# Sheet4.net
KiCad netlist of a schematic drawn in Altium Designer
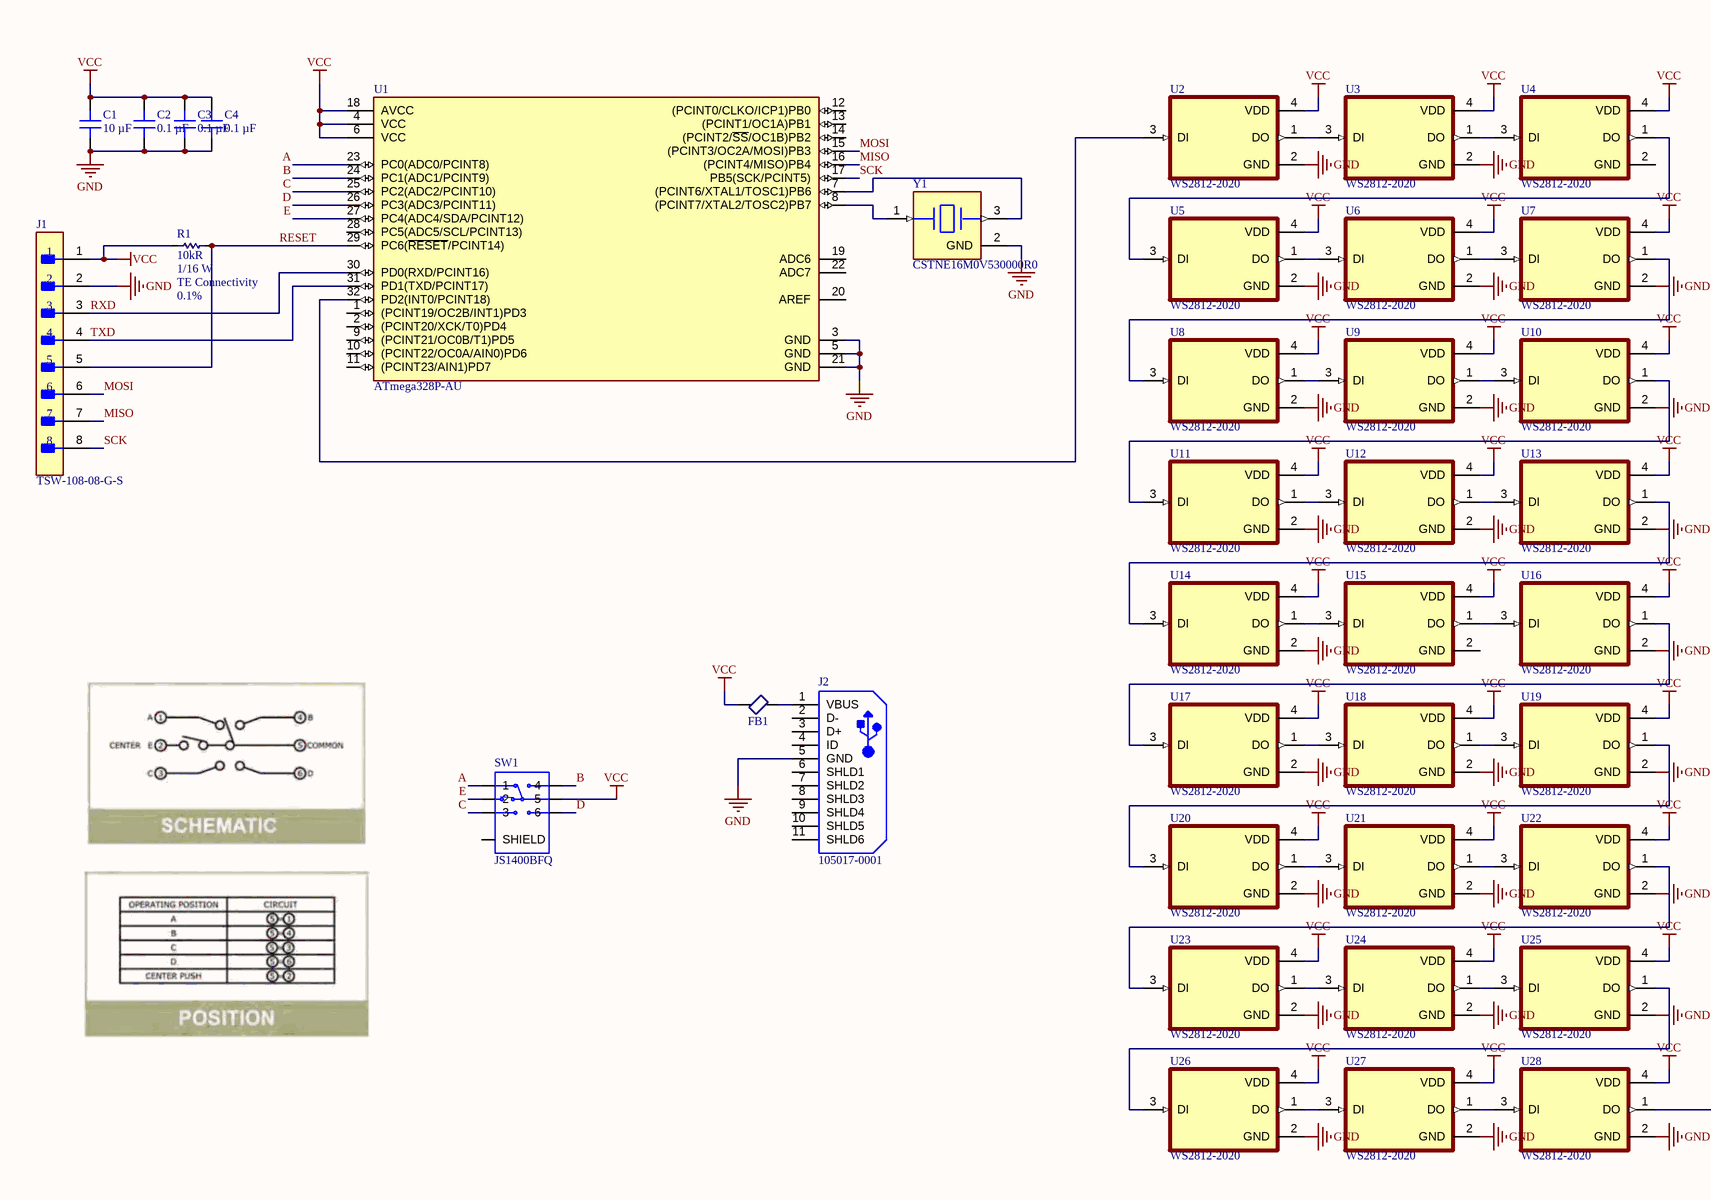
[diagram p0: Sheet4.SchDoc, left]
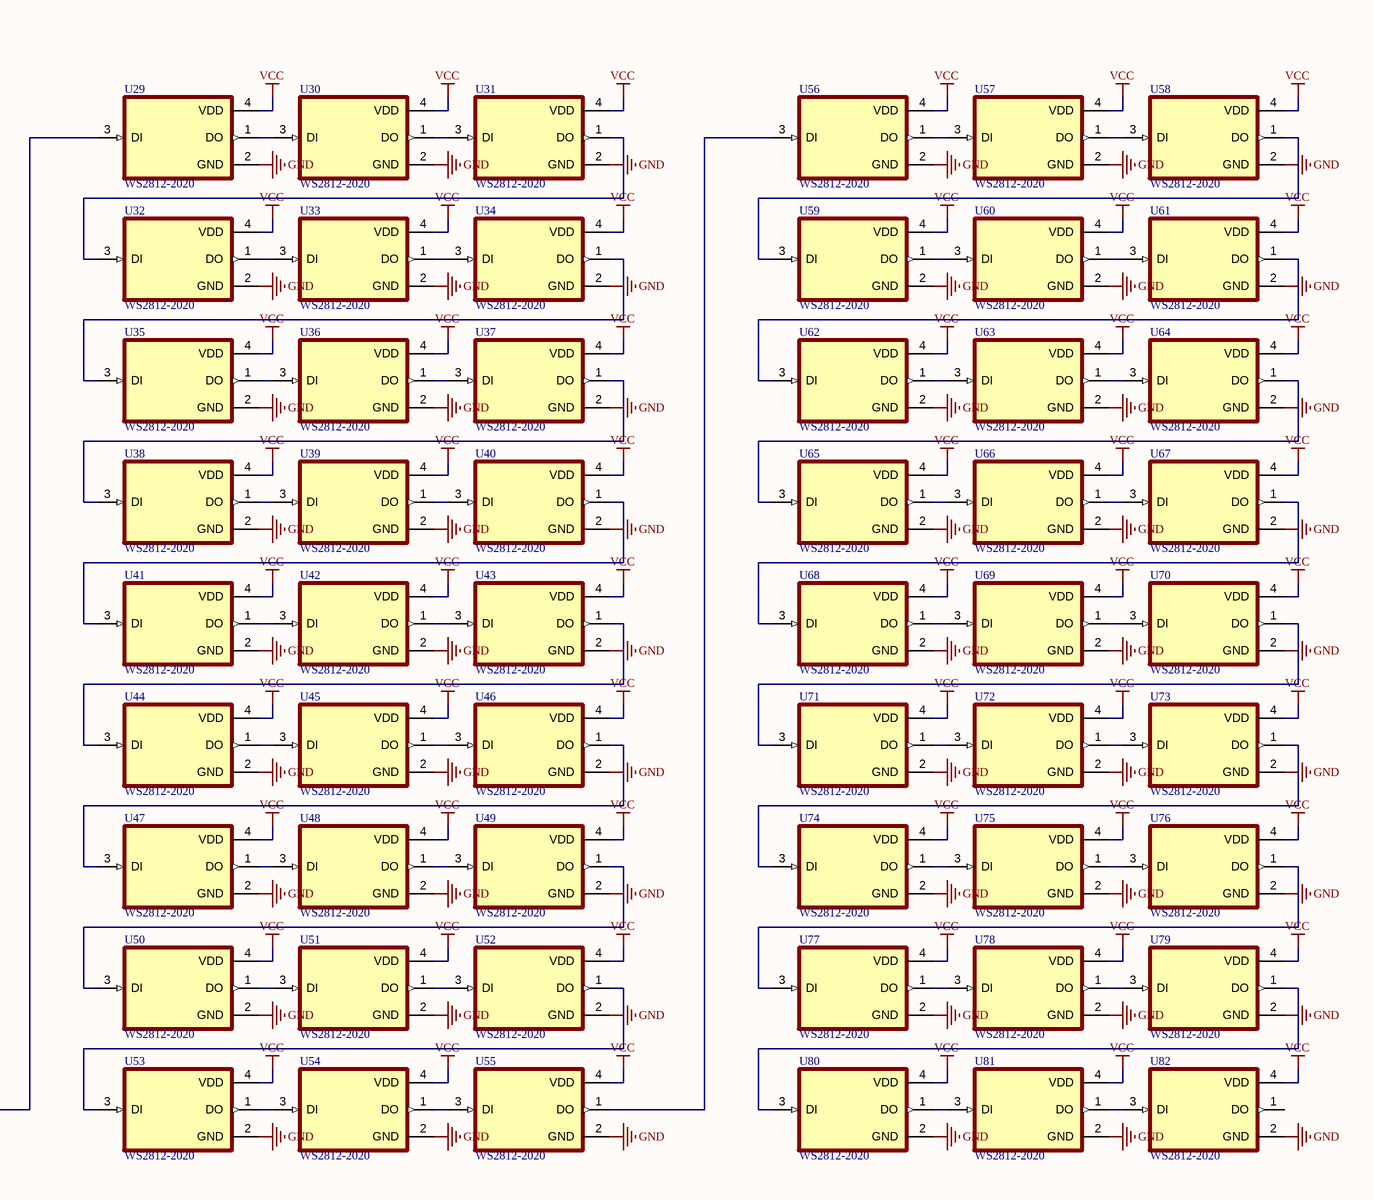
[diagram p1: Sheet4.SchDoc, right]

(export (version "E")
  (design (tool "Eeschema 10.0.6"))
  (components
    (comp (ref "C1")
      (value "10 µF")
      (footprint "CAP 0402_1005")
      (description "CAP CER 10UF 10V X5R 0402")
      (fields
        (field (name "PART NUMBER") "CL05A106MP5NUNC")
        (field (name "MANUFACTURER") "Samsung Electro-Mechanics")
      )
      (libsource (lib "Celestial Altium Library - altium_library") (part "Capacitor"))
    )
    (comp (ref "C2")
      (value "0.1 µF")
      (footprint "CAP 0402_1005")
      (description "CAP CER 0.1UF 10V X5R 0402")
      (fields
        (field (name "PART NUMBER") "CL05A104KP5NNNC")
        (field (name "MANUFACTURER") "Samsung Electro-Mechanics")
      )
      (libsource (lib "Celestial Altium Library - altium_library") (part "Capacitor"))
    )
    (comp (ref "C3")
      (value "0.1 µF")
      (footprint "CAP 0402_1005")
      (description "CAP CER 0.1UF 10V X5R 0402")
      (fields
        (field (name "PART NUMBER") "CL05A104KP5NNNC")
        (field (name "MANUFACTURER") "Samsung Electro-Mechanics")
      )
      (libsource (lib "Celestial Altium Library - altium_library") (part "Capacitor"))
    )
    (comp (ref "C4")
      (value "0.1 µF")
      (footprint "CAP 0402_1005")
      (description "CAP CER 0.1UF 10V X5R 0402")
      (fields
        (field (name "PART NUMBER") "CL05A104KP5NNNC")
        (field (name "MANUFACTURER") "Samsung Electro-Mechanics")
      )
      (libsource (lib "Celestial Altium Library - altium_library") (part "Capacitor"))
    )
    (comp (ref "FB1")
      (value "FB_330R_1.5A_0603")
      (footprint "FP-BLM18-0_15-t0_5-IPC_C")
      (description "Ferrite Beads Multi-Layer 330Ohm 25% 100MHz 1.5A 70mOhm DCR 0603 Paper T/R")
      (libsource (lib "Kennesaw Motorsports") (part "5f30dd21d616792df468990f7003faa"))
    )
    (comp (ref "J1")
      (value "TSW-108-08-G-S")
      (footprint "FP-TSW-108-08-G-S-MFG")
      (description "CONN HEADER VERT 8POS 2.54MM")
      (fields
        (field (name "MANUFACTURER") "Samtec")
        (field (name "OCTOPART") "https://octopart.com/tsw-108-08-g-s-samtec-272653")
      )
      (libsource (lib "Altium Content Vault") (part "99ec2b232beb5d2356d4d77f6a047f0"))
    )
    (comp (ref "J2")
      (value "105017-0001")
      (footprint "USB-MICRO-B_V")
      (fields (field (name "MANUFACTURER") "Molex"))
      (libsource (lib "Altium Content Vault") (part "USB-5-6SHLD"))
    )
    (comp (ref "R1")
      (value "RN73C1E10KBTG")
      (footprint "FP-RN731E-IPC_B")
      (description "RES 10K 0402 1/16W, RN73C1E10KBTG")
      (fields
        (field (name "RESISTANCE") "10kR")
        (field (name "POWER") "1/16 W")
        (field (name "MANUFACTURER") "TE Connectivity")
        (field (name "TOLERANCE") "0.1%")
        (field (name "PARTNUMBER") "RN73C1J4R99BTD")
        (field (name "SOURCE") "GoodResistor.SchLib")
      )
      (libsource (lib "Kennesaw Motorsports") (part "RN73C1E1K0BTD"))
    )
    (comp (ref "SW1")
      (value "JS1400BFQ")
      (footprint "SW_JS1400BFQ")
      (description "Navigation Switch, 2 - Axis Digital (Mechanical Switch) Output")
      (fields (field (name "DIGI-KEY_PART_NUMBER") "EG5858-ND") (field (name "MF") "E-Switch"))
      (libsource (lib "Kennesaw Motorsports") (part "JS1400BFQ"))
    )
    (comp (ref "U1")
      (value "ATmega328P-AU")
      (footprint "FP-32A-MFG")
      (description "IC MCU 8BIT 32KB FLASH 32TQFP")
      (fields
        (field (name "MANUFACTURER") "Microchip")
        (field (name "OCTOPART") "https://octopart.com/atmega328p-au-microchip-77760215")
      )
      (libsource (lib "Altium Content Vault") (part "f5fbdcb2c0c597ef7d3dd1575aef21a"))
    )
    (comp (ref "U2")
      (value "WS2812-2020")
      (footprint "LED_WS2812-2020")
      (description "Intelligent control LED integrated light source, WS2812-2020")
      (libsource (lib "Kennesaw Motorsports") (part "WS2812-2020"))
    )
    (comp (ref "U3")
      (value "WS2812-2020")
      (footprint "LED_WS2812-2020")
      (description "Intelligent control LED integrated light source, WS2812-2020")
      (libsource (lib "Kennesaw Motorsports") (part "WS2812-2020"))
    )
    (comp (ref "U4")
      (value "WS2812-2020")
      (footprint "LED_WS2812-2020")
      (description "Intelligent control LED integrated light source, WS2812-2020")
      (libsource (lib "Kennesaw Motorsports") (part "WS2812-2020"))
    )
    (comp (ref "U5")
      (value "WS2812-2020")
      (footprint "LED_WS2812-2020")
      (description "Intelligent control LED integrated light source, WS2812-2020")
      (libsource (lib "Kennesaw Motorsports") (part "WS2812-2020"))
    )
    (comp (ref "U6")
      (value "WS2812-2020")
      (footprint "LED_WS2812-2020")
      (description "Intelligent control LED integrated light source, WS2812-2020")
      (libsource (lib "Kennesaw Motorsports") (part "WS2812-2020"))
    )
    (comp (ref "U7")
      (value "WS2812-2020")
      (footprint "LED_WS2812-2020")
      (description "Intelligent control LED integrated light source, WS2812-2020")
      (libsource (lib "Kennesaw Motorsports") (part "WS2812-2020"))
    )
    (comp (ref "U8")
      (value "WS2812-2020")
      (footprint "LED_WS2812-2020")
      (description "Intelligent control LED integrated light source, WS2812-2020")
      (libsource (lib "Kennesaw Motorsports") (part "WS2812-2020"))
    )
    (comp (ref "U9")
      (value "WS2812-2020")
      (footprint "LED_WS2812-2020")
      (description "Intelligent control LED integrated light source, WS2812-2020")
      (libsource (lib "Kennesaw Motorsports") (part "WS2812-2020"))
    )
    (comp (ref "U10")
      (value "WS2812-2020")
      (footprint "LED_WS2812-2020")
      (description "Intelligent control LED integrated light source, WS2812-2020")
      (libsource (lib "Kennesaw Motorsports") (part "WS2812-2020"))
    )
    (comp (ref "U11")
      (value "WS2812-2020")
      (footprint "LED_WS2812-2020")
      (description "Intelligent control LED integrated light source, WS2812-2020")
      (libsource (lib "Kennesaw Motorsports") (part "WS2812-2020"))
    )
    (comp (ref "U12")
      (value "WS2812-2020")
      (footprint "LED_WS2812-2020")
      (description "Intelligent control LED integrated light source, WS2812-2020")
      (libsource (lib "Kennesaw Motorsports") (part "WS2812-2020"))
    )
    (comp (ref "U13")
      (value "WS2812-2020")
      (footprint "LED_WS2812-2020")
      (description "Intelligent control LED integrated light source, WS2812-2020")
      (libsource (lib "Kennesaw Motorsports") (part "WS2812-2020"))
    )
    (comp (ref "U14")
      (value "WS2812-2020")
      (footprint "LED_WS2812-2020")
      (description "Intelligent control LED integrated light source, WS2812-2020")
      (libsource (lib "Kennesaw Motorsports") (part "WS2812-2020"))
    )
    (comp (ref "U15")
      (value "WS2812-2020")
      (footprint "LED_WS2812-2020")
      (description "Intelligent control LED integrated light source, WS2812-2020")
      (libsource (lib "Kennesaw Motorsports") (part "WS2812-2020"))
    )
    (comp (ref "U16")
      (value "WS2812-2020")
      (footprint "LED_WS2812-2020")
      (description "Intelligent control LED integrated light source, WS2812-2020")
      (libsource (lib "Kennesaw Motorsports") (part "WS2812-2020"))
    )
    (comp (ref "U17")
      (value "WS2812-2020")
      (footprint "LED_WS2812-2020")
      (description "Intelligent control LED integrated light source, WS2812-2020")
      (libsource (lib "Kennesaw Motorsports") (part "WS2812-2020"))
    )
    (comp (ref "U18")
      (value "WS2812-2020")
      (footprint "LED_WS2812-2020")
      (description "Intelligent control LED integrated light source, WS2812-2020")
      (libsource (lib "Kennesaw Motorsports") (part "WS2812-2020"))
    )
    (comp (ref "U19")
      (value "WS2812-2020")
      (footprint "LED_WS2812-2020")
      (description "Intelligent control LED integrated light source, WS2812-2020")
      (libsource (lib "Kennesaw Motorsports") (part "WS2812-2020"))
    )
    (comp (ref "U20")
      (value "WS2812-2020")
      (footprint "LED_WS2812-2020")
      (description "Intelligent control LED integrated light source, WS2812-2020")
      (libsource (lib "Kennesaw Motorsports") (part "WS2812-2020"))
    )
    (comp (ref "U21")
      (value "WS2812-2020")
      (footprint "LED_WS2812-2020")
      (description "Intelligent control LED integrated light source, WS2812-2020")
      (libsource (lib "Kennesaw Motorsports") (part "WS2812-2020"))
    )
    (comp (ref "U22")
      (value "WS2812-2020")
      (footprint "LED_WS2812-2020")
      (description "Intelligent control LED integrated light source, WS2812-2020")
      (libsource (lib "Kennesaw Motorsports") (part "WS2812-2020"))
    )
    (comp (ref "U23")
      (value "WS2812-2020")
      (footprint "LED_WS2812-2020")
      (description "Intelligent control LED integrated light source, WS2812-2020")
      (libsource (lib "Kennesaw Motorsports") (part "WS2812-2020"))
    )
    (comp (ref "U24")
      (value "WS2812-2020")
      (footprint "LED_WS2812-2020")
      (description "Intelligent control LED integrated light source, WS2812-2020")
      (libsource (lib "Kennesaw Motorsports") (part "WS2812-2020"))
    )
    (comp (ref "U25")
      (value "WS2812-2020")
      (footprint "LED_WS2812-2020")
      (description "Intelligent control LED integrated light source, WS2812-2020")
      (libsource (lib "Kennesaw Motorsports") (part "WS2812-2020"))
    )
    (comp (ref "U26")
      (value "WS2812-2020")
      (footprint "LED_WS2812-2020")
      (description "Intelligent control LED integrated light source, WS2812-2020")
      (libsource (lib "Kennesaw Motorsports") (part "WS2812-2020"))
    )
    (comp (ref "U27")
      (value "WS2812-2020")
      (footprint "LED_WS2812-2020")
      (description "Intelligent control LED integrated light source, WS2812-2020")
      (libsource (lib "Kennesaw Motorsports") (part "WS2812-2020"))
    )
    (comp (ref "U28")
      (value "WS2812-2020")
      (footprint "LED_WS2812-2020")
      (description "Intelligent control LED integrated light source, WS2812-2020")
      (libsource (lib "Kennesaw Motorsports") (part "WS2812-2020"))
    )
    (comp (ref "U29")
      (value "WS2812-2020")
      (footprint "LED_WS2812-2020")
      (description "Intelligent control LED integrated light source, WS2812-2020")
      (libsource (lib "Kennesaw Motorsports") (part "WS2812-2020"))
    )
    (comp (ref "U30")
      (value "WS2812-2020")
      (footprint "LED_WS2812-2020")
      (description "Intelligent control LED integrated light source, WS2812-2020")
      (libsource (lib "Kennesaw Motorsports") (part "WS2812-2020"))
    )
    (comp (ref "U31")
      (value "WS2812-2020")
      (footprint "LED_WS2812-2020")
      (description "Intelligent control LED integrated light source, WS2812-2020")
      (libsource (lib "Kennesaw Motorsports") (part "WS2812-2020"))
    )
    (comp (ref "U32")
      (value "WS2812-2020")
      (footprint "LED_WS2812-2020")
      (description "Intelligent control LED integrated light source, WS2812-2020")
      (libsource (lib "Kennesaw Motorsports") (part "WS2812-2020"))
    )
    (comp (ref "U33")
      (value "WS2812-2020")
      (footprint "LED_WS2812-2020")
      (description "Intelligent control LED integrated light source, WS2812-2020")
      (libsource (lib "Kennesaw Motorsports") (part "WS2812-2020"))
    )
    (comp (ref "U34")
      (value "WS2812-2020")
      (footprint "LED_WS2812-2020")
      (description "Intelligent control LED integrated light source, WS2812-2020")
      (libsource (lib "Kennesaw Motorsports") (part "WS2812-2020"))
    )
    (comp (ref "U35")
      (value "WS2812-2020")
      (footprint "LED_WS2812-2020")
      (description "Intelligent control LED integrated light source, WS2812-2020")
      (libsource (lib "Kennesaw Motorsports") (part "WS2812-2020"))
    )
    (comp (ref "U36")
      (value "WS2812-2020")
      (footprint "LED_WS2812-2020")
      (description "Intelligent control LED integrated light source, WS2812-2020")
      (libsource (lib "Kennesaw Motorsports") (part "WS2812-2020"))
    )
    (comp (ref "U37")
      (value "WS2812-2020")
      (footprint "LED_WS2812-2020")
      (description "Intelligent control LED integrated light source, WS2812-2020")
      (libsource (lib "Kennesaw Motorsports") (part "WS2812-2020"))
    )
    (comp (ref "U38")
      (value "WS2812-2020")
      (footprint "LED_WS2812-2020")
      (description "Intelligent control LED integrated light source, WS2812-2020")
      (libsource (lib "Kennesaw Motorsports") (part "WS2812-2020"))
    )
    (comp (ref "U39")
      (value "WS2812-2020")
      (footprint "LED_WS2812-2020")
      (description "Intelligent control LED integrated light source, WS2812-2020")
      (libsource (lib "Kennesaw Motorsports") (part "WS2812-2020"))
    )
    (comp (ref "U40")
      (value "WS2812-2020")
      (footprint "LED_WS2812-2020")
      (description "Intelligent control LED integrated light source, WS2812-2020")
      (libsource (lib "Kennesaw Motorsports") (part "WS2812-2020"))
    )
    (comp (ref "U41")
      (value "WS2812-2020")
      (footprint "LED_WS2812-2020")
      (description "Intelligent control LED integrated light source, WS2812-2020")
      (libsource (lib "Kennesaw Motorsports") (part "WS2812-2020"))
    )
    (comp (ref "U42")
      (value "WS2812-2020")
      (footprint "LED_WS2812-2020")
      (description "Intelligent control LED integrated light source, WS2812-2020")
      (libsource (lib "Kennesaw Motorsports") (part "WS2812-2020"))
    )
    (comp (ref "U43")
      (value "WS2812-2020")
      (footprint "LED_WS2812-2020")
      (description "Intelligent control LED integrated light source, WS2812-2020")
      (libsource (lib "Kennesaw Motorsports") (part "WS2812-2020"))
    )
    (comp (ref "U44")
      (value "WS2812-2020")
      (footprint "LED_WS2812-2020")
      (description "Intelligent control LED integrated light source, WS2812-2020")
      (libsource (lib "Kennesaw Motorsports") (part "WS2812-2020"))
    )
    (comp (ref "U45")
      (value "WS2812-2020")
      (footprint "LED_WS2812-2020")
      (description "Intelligent control LED integrated light source, WS2812-2020")
      (libsource (lib "Kennesaw Motorsports") (part "WS2812-2020"))
    )
    (comp (ref "U46")
      (value "WS2812-2020")
      (footprint "LED_WS2812-2020")
      (description "Intelligent control LED integrated light source, WS2812-2020")
      (libsource (lib "Kennesaw Motorsports") (part "WS2812-2020"))
    )
    (comp (ref "U47")
      (value "WS2812-2020")
      (footprint "LED_WS2812-2020")
      (description "Intelligent control LED integrated light source, WS2812-2020")
      (libsource (lib "Kennesaw Motorsports") (part "WS2812-2020"))
    )
    (comp (ref "U48")
      (value "WS2812-2020")
      (footprint "LED_WS2812-2020")
      (description "Intelligent control LED integrated light source, WS2812-2020")
      (libsource (lib "Kennesaw Motorsports") (part "WS2812-2020"))
    )
    (comp (ref "U49")
      (value "WS2812-2020")
      (footprint "LED_WS2812-2020")
      (description "Intelligent control LED integrated light source, WS2812-2020")
      (libsource (lib "Kennesaw Motorsports") (part "WS2812-2020"))
    )
    (comp (ref "U50")
      (value "WS2812-2020")
      (footprint "LED_WS2812-2020")
      (description "Intelligent control LED integrated light source, WS2812-2020")
      (libsource (lib "Kennesaw Motorsports") (part "WS2812-2020"))
    )
    (comp (ref "U51")
      (value "WS2812-2020")
      (footprint "LED_WS2812-2020")
      (description "Intelligent control LED integrated light source, WS2812-2020")
      (libsource (lib "Kennesaw Motorsports") (part "WS2812-2020"))
    )
    (comp (ref "U52")
      (value "WS2812-2020")
      (footprint "LED_WS2812-2020")
      (description "Intelligent control LED integrated light source, WS2812-2020")
      (libsource (lib "Kennesaw Motorsports") (part "WS2812-2020"))
    )
    (comp (ref "U53")
      (value "WS2812-2020")
      (footprint "LED_WS2812-2020")
      (description "Intelligent control LED integrated light source, WS2812-2020")
      (libsource (lib "Kennesaw Motorsports") (part "WS2812-2020"))
    )
    (comp (ref "U54")
      (value "WS2812-2020")
      (footprint "LED_WS2812-2020")
      (description "Intelligent control LED integrated light source, WS2812-2020")
      (libsource (lib "Kennesaw Motorsports") (part "WS2812-2020"))
    )
    (comp (ref "U55")
      (value "WS2812-2020")
      (footprint "LED_WS2812-2020")
      (description "Intelligent control LED integrated light source, WS2812-2020")
      (libsource (lib "Kennesaw Motorsports") (part "WS2812-2020"))
    )
    (comp (ref "U56")
      (value "WS2812-2020")
      (footprint "LED_WS2812-2020")
      (description "Intelligent control LED integrated light source, WS2812-2020")
      (libsource (lib "Kennesaw Motorsports") (part "WS2812-2020"))
    )
    (comp (ref "U57")
      (value "WS2812-2020")
      (footprint "LED_WS2812-2020")
      (description "Intelligent control LED integrated light source, WS2812-2020")
      (libsource (lib "Kennesaw Motorsports") (part "WS2812-2020"))
    )
    (comp (ref "U58")
      (value "WS2812-2020")
      (footprint "LED_WS2812-2020")
      (description "Intelligent control LED integrated light source, WS2812-2020")
      (libsource (lib "Kennesaw Motorsports") (part "WS2812-2020"))
    )
    (comp (ref "U59")
      (value "WS2812-2020")
      (footprint "LED_WS2812-2020")
      (description "Intelligent control LED integrated light source, WS2812-2020")
      (libsource (lib "Kennesaw Motorsports") (part "WS2812-2020"))
    )
    (comp (ref "U60")
      (value "WS2812-2020")
      (footprint "LED_WS2812-2020")
      (description "Intelligent control LED integrated light source, WS2812-2020")
      (libsource (lib "Kennesaw Motorsports") (part "WS2812-2020"))
    )
    (comp (ref "U61")
      (value "WS2812-2020")
      (footprint "LED_WS2812-2020")
      (description "Intelligent control LED integrated light source, WS2812-2020")
      (libsource (lib "Kennesaw Motorsports") (part "WS2812-2020"))
    )
    (comp (ref "U62")
      (value "WS2812-2020")
      (footprint "LED_WS2812-2020")
      (description "Intelligent control LED integrated light source, WS2812-2020")
      (libsource (lib "Kennesaw Motorsports") (part "WS2812-2020"))
    )
    (comp (ref "U63")
      (value "WS2812-2020")
      (footprint "LED_WS2812-2020")
      (description "Intelligent control LED integrated light source, WS2812-2020")
      (libsource (lib "Kennesaw Motorsports") (part "WS2812-2020"))
    )
    (comp (ref "U64")
      (value "WS2812-2020")
      (footprint "LED_WS2812-2020")
      (description "Intelligent control LED integrated light source, WS2812-2020")
      (libsource (lib "Kennesaw Motorsports") (part "WS2812-2020"))
    )
    (comp (ref "U65")
      (value "WS2812-2020")
      (footprint "LED_WS2812-2020")
      (description "Intelligent control LED integrated light source, WS2812-2020")
      (libsource (lib "Kennesaw Motorsports") (part "WS2812-2020"))
    )
    (comp (ref "U66")
      (value "WS2812-2020")
      (footprint "LED_WS2812-2020")
      (description "Intelligent control LED integrated light source, WS2812-2020")
      (libsource (lib "Kennesaw Motorsports") (part "WS2812-2020"))
    )
    (comp (ref "U67")
      (value "WS2812-2020")
      (footprint "LED_WS2812-2020")
      (description "Intelligent control LED integrated light source, WS2812-2020")
      (libsource (lib "Kennesaw Motorsports") (part "WS2812-2020"))
    )
    (comp (ref "U68")
      (value "WS2812-2020")
      (footprint "LED_WS2812-2020")
      (description "Intelligent control LED integrated light source, WS2812-2020")
      (libsource (lib "Kennesaw Motorsports") (part "WS2812-2020"))
    )
    (comp (ref "U69")
      (value "WS2812-2020")
      (footprint "LED_WS2812-2020")
      (description "Intelligent control LED integrated light source, WS2812-2020")
      (libsource (lib "Kennesaw Motorsports") (part "WS2812-2020"))
    )
    (comp (ref "U70")
      (value "WS2812-2020")
      (footprint "LED_WS2812-2020")
      (description "Intelligent control LED integrated light source, WS2812-2020")
      (libsource (lib "Kennesaw Motorsports") (part "WS2812-2020"))
    )
    (comp (ref "U71")
      (value "WS2812-2020")
      (footprint "LED_WS2812-2020")
      (description "Intelligent control LED integrated light source, WS2812-2020")
      (libsource (lib "Kennesaw Motorsports") (part "WS2812-2020"))
    )
    (comp (ref "U72")
      (value "WS2812-2020")
      (footprint "LED_WS2812-2020")
      (description "Intelligent control LED integrated light source, WS2812-2020")
      (libsource (lib "Kennesaw Motorsports") (part "WS2812-2020"))
    )
    (comp (ref "U73")
      (value "WS2812-2020")
      (footprint "LED_WS2812-2020")
      (description "Intelligent control LED integrated light source, WS2812-2020")
      (libsource (lib "Kennesaw Motorsports") (part "WS2812-2020"))
    )
    (comp (ref "U74")
      (value "WS2812-2020")
      (footprint "LED_WS2812-2020")
      (description "Intelligent control LED integrated light source, WS2812-2020")
      (libsource (lib "Kennesaw Motorsports") (part "WS2812-2020"))
    )
    (comp (ref "U75")
      (value "WS2812-2020")
      (footprint "LED_WS2812-2020")
      (description "Intelligent control LED integrated light source, WS2812-2020")
      (libsource (lib "Kennesaw Motorsports") (part "WS2812-2020"))
    )
    (comp (ref "U76")
      (value "WS2812-2020")
      (footprint "LED_WS2812-2020")
      (description "Intelligent control LED integrated light source, WS2812-2020")
      (libsource (lib "Kennesaw Motorsports") (part "WS2812-2020"))
    )
    (comp (ref "U77")
      (value "WS2812-2020")
      (footprint "LED_WS2812-2020")
      (description "Intelligent control LED integrated light source, WS2812-2020")
      (libsource (lib "Kennesaw Motorsports") (part "WS2812-2020"))
    )
    (comp (ref "U78")
      (value "WS2812-2020")
      (footprint "LED_WS2812-2020")
      (description "Intelligent control LED integrated light source, WS2812-2020")
      (libsource (lib "Kennesaw Motorsports") (part "WS2812-2020"))
    )
    (comp (ref "U79")
      (value "WS2812-2020")
      (footprint "LED_WS2812-2020")
      (description "Intelligent control LED integrated light source, WS2812-2020")
      (libsource (lib "Kennesaw Motorsports") (part "WS2812-2020"))
    )
    (comp (ref "U80")
      (value "WS2812-2020")
      (footprint "LED_WS2812-2020")
      (description "Intelligent control LED integrated light source, WS2812-2020")
      (libsource (lib "Kennesaw Motorsports") (part "WS2812-2020"))
    )
    (comp (ref "U81")
      (value "WS2812-2020")
      (footprint "LED_WS2812-2020")
      (description "Intelligent control LED integrated light source, WS2812-2020")
      (libsource (lib "Kennesaw Motorsports") (part "WS2812-2020"))
    )
    (comp (ref "U82")
      (value "WS2812-2020")
      (footprint "LED_WS2812-2020")
      (description "Intelligent control LED integrated light source, WS2812-2020")
      (libsource (lib "Kennesaw Motorsports") (part "WS2812-2020"))
    )
    (comp (ref "Y1")
      (value "CSTNE16M0V530000R0")
      (footprint "FP-CSTNE16M0V530000R0-MFG")
      (description "16MHz Ceramic Resonator Built in Capacitor 15pF ±0.3% 40 Ohms -40°C ~ 85°C Surface Mount")
      (fields (field (name "TOLERANCE") "0.5%"))
      (libsource (lib "Altium Content Vault") (part "f88508b02107a2c8e6f46217c19d2b8"))
    )
  )
  (nets
    (net (code "1") (name "/A") (class "Default")
      (node (ref "SW1") (pin "1") (pinfunction "1_1") (pintype "passive"))
      (node (ref "U1") (pin "23") (pinfunction "PC0(ADC0/PCINT8)_23") (pintype "bidirectional"))
    )
    (net (code "2") (name "/B") (class "Default")
      (node (ref "SW1") (pin "4") (pinfunction "4_4") (pintype "passive"))
      (node (ref "U1") (pin "24") (pinfunction "PC1(ADC1/PCINT9)_24") (pintype "bidirectional"))
    )
    (net (code "3") (name "/C") (class "Default")
      (node (ref "SW1") (pin "3") (pinfunction "3_3") (pintype "passive"))
      (node (ref "U1") (pin "25") (pinfunction "PC2(ADC2/PCINT10)_25") (pintype "bidirectional"))
    )
    (net (code "4") (name "/D") (class "Default")
      (node (ref "SW1") (pin "6") (pinfunction "6_6") (pintype "passive"))
      (node (ref "U1") (pin "26") (pinfunction "PC3(ADC3/PCINT11)_26") (pintype "bidirectional"))
    )
    (net (code "5") (name "/E") (class "Default")
      (node (ref "SW1") (pin "2") (pinfunction "2_2") (pintype "passive"))
      (node (ref "U1") (pin "27") (pinfunction "PC4(ADC4/SDA/PCINT12)_27") (pintype "bidirectional"))
    )
    (net (code "6") (name "/MISO") (class "Default")
      (node (ref "J1") (pin "7") (pinfunction "7_7") (pintype "passive"))
      (node (ref "U1") (pin "16") (pinfunction "(PCINT4/MISO)PB4_16") (pintype "bidirectional"))
    )
    (net (code "7") (name "/MOSI") (class "Default")
      (node (ref "J1") (pin "6") (pinfunction "6_6") (pintype "passive"))
      (node (ref "U1") (pin "15") (pinfunction "(PCINT3/OC2A/MOSI)PB3_15") (pintype "bidirectional"))
    )
    (net (code "8") (name "/RESET") (class "Default")
      (node (ref "J1") (pin "5") (pinfunction "5_5") (pintype "passive"))
      (node (ref "R1") (pin "1") (pinfunction "1_1") (pintype "passive"))
      (node (ref "U1") (pin "29") (pinfunction "PC6(~{RESET}/PCINT14)_29") (pintype "bidirectional"))
    )
    (net (code "9") (name "/RXD") (class "Default")
      (node (ref "J1") (pin "3") (pinfunction "3_3") (pintype "passive"))
      (node (ref "U1") (pin "30") (pinfunction "PD0(RXD/PCINT16)_30") (pintype "bidirectional"))
    )
    (net (code "10") (name "/SCK") (class "Default")
      (node (ref "J1") (pin "8") (pinfunction "8_8") (pintype "passive"))
      (node (ref "U1") (pin "17") (pinfunction "PB5(SCK/PCINT5)_17") (pintype "bidirectional"))
    )
    (net (code "11") (name "/TXD") (class "Default")
      (node (ref "J1") (pin "4") (pinfunction "4_4") (pintype "passive"))
      (node (ref "U1") (pin "31") (pinfunction "PD1(TXD/PCINT17)_31") (pintype "bidirectional"))
    )
    (net (code "12") (name "GND") (class "Default")
      (node (ref "C1") (pin "1") (pinfunction "1_1") (pintype "passive"))
      (node (ref "C2") (pin "1") (pinfunction "1_1") (pintype "passive"))
      (node (ref "C3") (pin "1") (pinfunction "1_1") (pintype "passive"))
      (node (ref "C4") (pin "1") (pinfunction "1_1") (pintype "passive"))
      (node (ref "J1") (pin "2") (pinfunction "2_2") (pintype "passive"))
      (node (ref "J2") (pin "5") (pinfunction "GND_5") (pintype "passive"))
      (node (ref "U1") (pin "21") (pinfunction "GND_21") (pintype "power_in"))
      (node (ref "U1") (pin "3") (pinfunction "GND_3") (pintype "power_in"))
      (node (ref "U1") (pin "5") (pinfunction "GND_5") (pintype "power_in"))
      (node (ref "U10") (pin "2") (pinfunction "GND_2") (pintype "power_in"))
      (node (ref "U11") (pin "2") (pinfunction "GND_2") (pintype "power_in"))
      (node (ref "U12") (pin "2") (pinfunction "GND_2") (pintype "power_in"))
      (node (ref "U13") (pin "2") (pinfunction "GND_2") (pintype "power_in"))
      (node (ref "U14") (pin "2") (pinfunction "GND_2") (pintype "power_in"))
      (node (ref "U16") (pin "2") (pinfunction "GND_2") (pintype "power_in"))
      (node (ref "U17") (pin "2") (pinfunction "GND_2") (pintype "power_in"))
      (node (ref "U18") (pin "2") (pinfunction "GND_2") (pintype "power_in"))
      (node (ref "U19") (pin "2") (pinfunction "GND_2") (pintype "power_in"))
      (node (ref "U2") (pin "2") (pinfunction "GND_2") (pintype "power_in"))
      (node (ref "U20") (pin "2") (pinfunction "GND_2") (pintype "power_in"))
      (node (ref "U21") (pin "2") (pinfunction "GND_2") (pintype "power_in"))
      (node (ref "U22") (pin "2") (pinfunction "GND_2") (pintype "power_in"))
      (node (ref "U23") (pin "2") (pinfunction "GND_2") (pintype "power_in"))
      (node (ref "U24") (pin "2") (pinfunction "GND_2") (pintype "power_in"))
      (node (ref "U25") (pin "2") (pinfunction "GND_2") (pintype "power_in"))
      (node (ref "U26") (pin "2") (pinfunction "GND_2") (pintype "power_in"))
      (node (ref "U27") (pin "2") (pinfunction "GND_2") (pintype "power_in"))
      (node (ref "U28") (pin "2") (pinfunction "GND_2") (pintype "power_in"))
      (node (ref "U29") (pin "2") (pinfunction "GND_2") (pintype "power_in"))
      (node (ref "U3") (pin "2") (pinfunction "GND_2") (pintype "power_in"))
      (node (ref "U30") (pin "2") (pinfunction "GND_2") (pintype "power_in"))
      (node (ref "U31") (pin "2") (pinfunction "GND_2") (pintype "power_in"))
      (node (ref "U32") (pin "2") (pinfunction "GND_2") (pintype "power_in"))
      (node (ref "U33") (pin "2") (pinfunction "GND_2") (pintype "power_in"))
      (node (ref "U34") (pin "2") (pinfunction "GND_2") (pintype "power_in"))
      (node (ref "U35") (pin "2") (pinfunction "GND_2") (pintype "power_in"))
      (node (ref "U36") (pin "2") (pinfunction "GND_2") (pintype "power_in"))
      (node (ref "U37") (pin "2") (pinfunction "GND_2") (pintype "power_in"))
      (node (ref "U38") (pin "2") (pinfunction "GND_2") (pintype "power_in"))
      (node (ref "U39") (pin "2") (pinfunction "GND_2") (pintype "power_in"))
      (node (ref "U40") (pin "2") (pinfunction "GND_2") (pintype "power_in"))
      (node (ref "U41") (pin "2") (pinfunction "GND_2") (pintype "power_in"))
      (node (ref "U42") (pin "2") (pinfunction "GND_2") (pintype "power_in"))
      (node (ref "U43") (pin "2") (pinfunction "GND_2") (pintype "power_in"))
      (node (ref "U44") (pin "2") (pinfunction "GND_2") (pintype "power_in"))
      (node (ref "U45") (pin "2") (pinfunction "GND_2") (pintype "power_in"))
      (node (ref "U46") (pin "2") (pinfunction "GND_2") (pintype "power_in"))
      (node (ref "U47") (pin "2") (pinfunction "GND_2") (pintype "power_in"))
      (node (ref "U48") (pin "2") (pinfunction "GND_2") (pintype "power_in"))
      (node (ref "U49") (pin "2") (pinfunction "GND_2") (pintype "power_in"))
      (node (ref "U5") (pin "2") (pinfunction "GND_2") (pintype "power_in"))
      (node (ref "U50") (pin "2") (pinfunction "GND_2") (pintype "power_in"))
      (node (ref "U51") (pin "2") (pinfunction "GND_2") (pintype "power_in"))
      (node (ref "U52") (pin "2") (pinfunction "GND_2") (pintype "power_in"))
      (node (ref "U53") (pin "2") (pinfunction "GND_2") (pintype "power_in"))
      (node (ref "U54") (pin "2") (pinfunction "GND_2") (pintype "power_in"))
      (node (ref "U55") (pin "2") (pinfunction "GND_2") (pintype "power_in"))
      (node (ref "U56") (pin "2") (pinfunction "GND_2") (pintype "power_in"))
      (node (ref "U57") (pin "2") (pinfunction "GND_2") (pintype "power_in"))
      (node (ref "U58") (pin "2") (pinfunction "GND_2") (pintype "power_in"))
      (node (ref "U59") (pin "2") (pinfunction "GND_2") (pintype "power_in"))
      (node (ref "U6") (pin "2") (pinfunction "GND_2") (pintype "power_in"))
      (node (ref "U60") (pin "2") (pinfunction "GND_2") (pintype "power_in"))
      (node (ref "U61") (pin "2") (pinfunction "GND_2") (pintype "power_in"))
      (node (ref "U62") (pin "2") (pinfunction "GND_2") (pintype "power_in"))
      (node (ref "U63") (pin "2") (pinfunction "GND_2") (pintype "power_in"))
      (node (ref "U64") (pin "2") (pinfunction "GND_2") (pintype "power_in"))
      (node (ref "U65") (pin "2") (pinfunction "GND_2") (pintype "power_in"))
      (node (ref "U66") (pin "2") (pinfunction "GND_2") (pintype "power_in"))
      (node (ref "U67") (pin "2") (pinfunction "GND_2") (pintype "power_in"))
      (node (ref "U68") (pin "2") (pinfunction "GND_2") (pintype "power_in"))
      (node (ref "U69") (pin "2") (pinfunction "GND_2") (pintype "power_in"))
      (node (ref "U7") (pin "2") (pinfunction "GND_2") (pintype "power_in"))
      (node (ref "U70") (pin "2") (pinfunction "GND_2") (pintype "power_in"))
      (node (ref "U71") (pin "2") (pinfunction "GND_2") (pintype "power_in"))
      (node (ref "U72") (pin "2") (pinfunction "GND_2") (pintype "power_in"))
      (node (ref "U73") (pin "2") (pinfunction "GND_2") (pintype "power_in"))
      (node (ref "U74") (pin "2") (pinfunction "GND_2") (pintype "power_in"))
      (node (ref "U75") (pin "2") (pinfunction "GND_2") (pintype "power_in"))
      (node (ref "U76") (pin "2") (pinfunction "GND_2") (pintype "power_in"))
      (node (ref "U77") (pin "2") (pinfunction "GND_2") (pintype "power_in"))
      (node (ref "U78") (pin "2") (pinfunction "GND_2") (pintype "power_in"))
      (node (ref "U79") (pin "2") (pinfunction "GND_2") (pintype "power_in"))
      (node (ref "U8") (pin "2") (pinfunction "GND_2") (pintype "power_in"))
      (node (ref "U80") (pin "2") (pinfunction "GND_2") (pintype "power_in"))
      (node (ref "U81") (pin "2") (pinfunction "GND_2") (pintype "power_in"))
      (node (ref "U82") (pin "2") (pinfunction "GND_2") (pintype "power_in"))
      (node (ref "U9") (pin "2") (pinfunction "GND_2") (pintype "power_in"))
      (node (ref "Y1") (pin "2") (pinfunction "GND_2") (pintype "power_in"))
    )
    (net (code "13") (name "Net-(J2-VBUS)") (class "Default")
      (node (ref "FB1") (pin "2") (pinfunction "2_2") (pintype "passive"))
      (node (ref "J2") (pin "1") (pinfunction "VBUS_1") (pintype "passive"))
    )
    (net (code "14") (name "Net-(SW1-SHIELD-PadSH1)") (class "Default")
      (node (ref "SW1") (pin "SH1") (pinfunction "SHIELD_SH1") (pintype "passive"))
      (node (ref "SW1") (pin "SH2") (pinfunction "SHIELD_SH2") (pintype "passive"))
    )
    (net (code "15") (name "Net-(U1-(PCINT6{slash}XTAL1{slash}TOSC1)PB6)") (class "Default")
      (node (ref "U1") (pin "7") (pinfunction "(PCINT6/XTAL1/TOSC1)PB6_7") (pintype "bidirectional"))
      (node (ref "Y1") (pin "3") (pinfunction "Output_3") (pintype "output"))
    )
    (net (code "16") (name "Net-(U1-(PCINT7{slash}XTAL2{slash}TOSC2)PB7)") (class "Default")
      (node (ref "U1") (pin "8") (pinfunction "(PCINT7/XTAL2/TOSC2)PB7_8") (pintype "bidirectional"))
      (node (ref "Y1") (pin "1") (pinfunction "Input_1") (pintype "input"))
    )
    (net (code "17") (name "Net-(U1-PD2(INT0{slash}PCINT18))") (class "Default")
      (node (ref "U1") (pin "32") (pinfunction "PD2(INT0/PCINT18)_32") (pintype "bidirectional"))
      (node (ref "U2") (pin "3") (pinfunction "DI_3") (pintype "input"))
    )
    (net (code "18") (name "Net-(U2-DO)") (class "Default")
      (node (ref "U2") (pin "1") (pinfunction "DO_1") (pintype "output"))
      (node (ref "U3") (pin "3") (pinfunction "DI_3") (pintype "input"))
    )
    (net (code "19") (name "Net-(U3-DO)") (class "Default")
      (node (ref "U3") (pin "1") (pinfunction "DO_1") (pintype "output"))
      (node (ref "U4") (pin "3") (pinfunction "DI_3") (pintype "input"))
    )
    (net (code "20") (name "Net-(U4-DO)") (class "Default")
      (node (ref "U4") (pin "1") (pinfunction "DO_1") (pintype "output"))
      (node (ref "U5") (pin "3") (pinfunction "DI_3") (pintype "input"))
    )
    (net (code "21") (name "Net-(U5-DO)") (class "Default")
      (node (ref "U5") (pin "1") (pinfunction "DO_1") (pintype "output"))
      (node (ref "U6") (pin "3") (pinfunction "DI_3") (pintype "input"))
    )
    (net (code "22") (name "Net-(U6-DO)") (class "Default")
      (node (ref "U6") (pin "1") (pinfunction "DO_1") (pintype "output"))
      (node (ref "U7") (pin "3") (pinfunction "DI_3") (pintype "input"))
    )
    (net (code "23") (name "Net-(U7-DO)") (class "Default")
      (node (ref "U7") (pin "1") (pinfunction "DO_1") (pintype "output"))
      (node (ref "U8") (pin "3") (pinfunction "DI_3") (pintype "input"))
    )
    (net (code "24") (name "Net-(U8-DO)") (class "Default")
      (node (ref "U8") (pin "1") (pinfunction "DO_1") (pintype "output"))
      (node (ref "U9") (pin "3") (pinfunction "DI_3") (pintype "input"))
    )
    (net (code "25") (name "Net-(U10-DI)") (class "Default")
      (node (ref "U10") (pin "3") (pinfunction "DI_3") (pintype "input"))
      (node (ref "U9") (pin "1") (pinfunction "DO_1") (pintype "output"))
    )
    (net (code "26") (name "Net-(U10-DO)") (class "Default")
      (node (ref "U10") (pin "1") (pinfunction "DO_1") (pintype "output"))
      (node (ref "U11") (pin "3") (pinfunction "DI_3") (pintype "input"))
    )
    (net (code "27") (name "Net-(U11-DO)") (class "Default")
      (node (ref "U11") (pin "1") (pinfunction "DO_1") (pintype "output"))
      (node (ref "U12") (pin "3") (pinfunction "DI_3") (pintype "input"))
    )
    (net (code "28") (name "Net-(U12-DO)") (class "Default")
      (node (ref "U12") (pin "1") (pinfunction "DO_1") (pintype "output"))
      (node (ref "U13") (pin "3") (pinfunction "DI_3") (pintype "input"))
    )
    (net (code "29") (name "Net-(U13-DO)") (class "Default")
      (node (ref "U13") (pin "1") (pinfunction "DO_1") (pintype "output"))
      (node (ref "U14") (pin "3") (pinfunction "DI_3") (pintype "input"))
    )
    (net (code "30") (name "Net-(U14-DO)") (class "Default")
      (node (ref "U14") (pin "1") (pinfunction "DO_1") (pintype "output"))
      (node (ref "U15") (pin "3") (pinfunction "DI_3") (pintype "input"))
    )
    (net (code "31") (name "Net-(U15-DO)") (class "Default")
      (node (ref "U15") (pin "1") (pinfunction "DO_1") (pintype "output"))
      (node (ref "U16") (pin "3") (pinfunction "DI_3") (pintype "input"))
    )
    (net (code "32") (name "Net-(U16-DO)") (class "Default")
      (node (ref "U16") (pin "1") (pinfunction "DO_1") (pintype "output"))
      (node (ref "U17") (pin "3") (pinfunction "DI_3") (pintype "input"))
    )
    (net (code "33") (name "Net-(U17-DO)") (class "Default")
      (node (ref "U17") (pin "1") (pinfunction "DO_1") (pintype "output"))
      (node (ref "U18") (pin "3") (pinfunction "DI_3") (pintype "input"))
    )
    (net (code "34") (name "Net-(U18-DO)") (class "Default")
      (node (ref "U18") (pin "1") (pinfunction "DO_1") (pintype "output"))
      (node (ref "U19") (pin "3") (pinfunction "DI_3") (pintype "input"))
    )
    (net (code "35") (name "Net-(U19-DO)") (class "Default")
      (node (ref "U19") (pin "1") (pinfunction "DO_1") (pintype "output"))
      (node (ref "U20") (pin "3") (pinfunction "DI_3") (pintype "input"))
    )
    (net (code "36") (name "Net-(U20-DO)") (class "Default")
      (node (ref "U20") (pin "1") (pinfunction "DO_1") (pintype "output"))
      (node (ref "U21") (pin "3") (pinfunction "DI_3") (pintype "input"))
    )
    (net (code "37") (name "Net-(U21-DO)") (class "Default")
      (node (ref "U21") (pin "1") (pinfunction "DO_1") (pintype "output"))
      (node (ref "U22") (pin "3") (pinfunction "DI_3") (pintype "input"))
    )
    (net (code "38") (name "Net-(U22-DO)") (class "Default")
      (node (ref "U22") (pin "1") (pinfunction "DO_1") (pintype "output"))
      (node (ref "U23") (pin "3") (pinfunction "DI_3") (pintype "input"))
    )
    (net (code "39") (name "Net-(U23-DO)") (class "Default")
      (node (ref "U23") (pin "1") (pinfunction "DO_1") (pintype "output"))
      (node (ref "U24") (pin "3") (pinfunction "DI_3") (pintype "input"))
    )
    (net (code "40") (name "Net-(U24-DO)") (class "Default")
      (node (ref "U24") (pin "1") (pinfunction "DO_1") (pintype "output"))
      (node (ref "U25") (pin "3") (pinfunction "DI_3") (pintype "input"))
    )
    (net (code "41") (name "Net-(U25-DO)") (class "Default")
      (node (ref "U25") (pin "1") (pinfunction "DO_1") (pintype "output"))
      (node (ref "U26") (pin "3") (pinfunction "DI_3") (pintype "input"))
    )
    (net (code "42") (name "Net-(U26-DO)") (class "Default")
      (node (ref "U26") (pin "1") (pinfunction "DO_1") (pintype "output"))
      (node (ref "U27") (pin "3") (pinfunction "DI_3") (pintype "input"))
    )
    (net (code "43") (name "Net-(U27-DO)") (class "Default")
      (node (ref "U27") (pin "1") (pinfunction "DO_1") (pintype "output"))
      (node (ref "U28") (pin "3") (pinfunction "DI_3") (pintype "input"))
    )
    (net (code "44") (name "Net-(U28-DO)") (class "Default")
      (node (ref "U28") (pin "1") (pinfunction "DO_1") (pintype "output"))
      (node (ref "U29") (pin "3") (pinfunction "DI_3") (pintype "input"))
    )
    (net (code "45") (name "Net-(U29-DO)") (class "Default")
      (node (ref "U29") (pin "1") (pinfunction "DO_1") (pintype "output"))
      (node (ref "U30") (pin "3") (pinfunction "DI_3") (pintype "input"))
    )
    (net (code "46") (name "Net-(U30-DO)") (class "Default")
      (node (ref "U30") (pin "1") (pinfunction "DO_1") (pintype "output"))
      (node (ref "U31") (pin "3") (pinfunction "DI_3") (pintype "input"))
    )
    (net (code "47") (name "Net-(U31-DO)") (class "Default")
      (node (ref "U31") (pin "1") (pinfunction "DO_1") (pintype "output"))
      (node (ref "U32") (pin "3") (pinfunction "DI_3") (pintype "input"))
    )
    (net (code "48") (name "Net-(U32-DO)") (class "Default")
      (node (ref "U32") (pin "1") (pinfunction "DO_1") (pintype "output"))
      (node (ref "U33") (pin "3") (pinfunction "DI_3") (pintype "input"))
    )
    (net (code "49") (name "Net-(U33-DO)") (class "Default")
      (node (ref "U33") (pin "1") (pinfunction "DO_1") (pintype "output"))
      (node (ref "U34") (pin "3") (pinfunction "DI_3") (pintype "input"))
    )
    (net (code "50") (name "Net-(U34-DO)") (class "Default")
      (node (ref "U34") (pin "1") (pinfunction "DO_1") (pintype "output"))
      (node (ref "U35") (pin "3") (pinfunction "DI_3") (pintype "input"))
    )
    (net (code "51") (name "Net-(U35-DO)") (class "Default")
      (node (ref "U35") (pin "1") (pinfunction "DO_1") (pintype "output"))
      (node (ref "U36") (pin "3") (pinfunction "DI_3") (pintype "input"))
    )
    (net (code "52") (name "Net-(U36-DO)") (class "Default")
      (node (ref "U36") (pin "1") (pinfunction "DO_1") (pintype "output"))
      (node (ref "U37") (pin "3") (pinfunction "DI_3") (pintype "input"))
    )
    (net (code "53") (name "Net-(U37-DO)") (class "Default")
      (node (ref "U37") (pin "1") (pinfunction "DO_1") (pintype "output"))
      (node (ref "U38") (pin "3") (pinfunction "DI_3") (pintype "input"))
    )
    (net (code "54") (name "Net-(U38-DO)") (class "Default")
      (node (ref "U38") (pin "1") (pinfunction "DO_1") (pintype "output"))
      (node (ref "U39") (pin "3") (pinfunction "DI_3") (pintype "input"))
    )
    (net (code "55") (name "Net-(U39-DO)") (class "Default")
      (node (ref "U39") (pin "1") (pinfunction "DO_1") (pintype "output"))
      (node (ref "U40") (pin "3") (pinfunction "DI_3") (pintype "input"))
    )
    (net (code "56") (name "Net-(U40-DO)") (class "Default")
      (node (ref "U40") (pin "1") (pinfunction "DO_1") (pintype "output"))
      (node (ref "U41") (pin "3") (pinfunction "DI_3") (pintype "input"))
    )
    (net (code "57") (name "Net-(U41-DO)") (class "Default")
      (node (ref "U41") (pin "1") (pinfunction "DO_1") (pintype "output"))
      (node (ref "U42") (pin "3") (pinfunction "DI_3") (pintype "input"))
    )
    (net (code "58") (name "Net-(U42-DO)") (class "Default")
      (node (ref "U42") (pin "1") (pinfunction "DO_1") (pintype "output"))
      (node (ref "U43") (pin "3") (pinfunction "DI_3") (pintype "input"))
    )
    (net (code "59") (name "Net-(U43-DO)") (class "Default")
      (node (ref "U43") (pin "1") (pinfunction "DO_1") (pintype "output"))
      (node (ref "U44") (pin "3") (pinfunction "DI_3") (pintype "input"))
    )
    (net (code "60") (name "Net-(U44-DO)") (class "Default")
      (node (ref "U44") (pin "1") (pinfunction "DO_1") (pintype "output"))
      (node (ref "U45") (pin "3") (pinfunction "DI_3") (pintype "input"))
    )
    (net (code "61") (name "Net-(U45-DO)") (class "Default")
      (node (ref "U45") (pin "1") (pinfunction "DO_1") (pintype "output"))
      (node (ref "U46") (pin "3") (pinfunction "DI_3") (pintype "input"))
    )
    (net (code "62") (name "Net-(U46-DO)") (class "Default")
      (node (ref "U46") (pin "1") (pinfunction "DO_1") (pintype "output"))
      (node (ref "U47") (pin "3") (pinfunction "DI_3") (pintype "input"))
    )
    (net (code "63") (name "Net-(U47-DO)") (class "Default")
      (node (ref "U47") (pin "1") (pinfunction "DO_1") (pintype "output"))
      (node (ref "U48") (pin "3") (pinfunction "DI_3") (pintype "input"))
    )
    (net (code "64") (name "Net-(U48-DO)") (class "Default")
      (node (ref "U48") (pin "1") (pinfunction "DO_1") (pintype "output"))
      (node (ref "U49") (pin "3") (pinfunction "DI_3") (pintype "input"))
    )
    (net (code "65") (name "Net-(U49-DO)") (class "Default")
      (node (ref "U49") (pin "1") (pinfunction "DO_1") (pintype "output"))
      (node (ref "U50") (pin "3") (pinfunction "DI_3") (pintype "input"))
    )
    (net (code "66") (name "Net-(U50-DO)") (class "Default")
      (node (ref "U50") (pin "1") (pinfunction "DO_1") (pintype "output"))
      (node (ref "U51") (pin "3") (pinfunction "DI_3") (pintype "input"))
    )
    (net (code "67") (name "Net-(U51-DO)") (class "Default")
      (node (ref "U51") (pin "1") (pinfunction "DO_1") (pintype "output"))
      (node (ref "U52") (pin "3") (pinfunction "DI_3") (pintype "input"))
    )
    (net (code "68") (name "Net-(U52-DO)") (class "Default")
      (node (ref "U52") (pin "1") (pinfunction "DO_1") (pintype "output"))
      (node (ref "U53") (pin "3") (pinfunction "DI_3") (pintype "input"))
    )
    (net (code "69") (name "Net-(U53-DO)") (class "Default")
      (node (ref "U53") (pin "1") (pinfunction "DO_1") (pintype "output"))
      (node (ref "U54") (pin "3") (pinfunction "DI_3") (pintype "input"))
    )
    (net (code "70") (name "Net-(U54-DO)") (class "Default")
      (node (ref "U54") (pin "1") (pinfunction "DO_1") (pintype "output"))
      (node (ref "U55") (pin "3") (pinfunction "DI_3") (pintype "input"))
    )
    (net (code "71") (name "Net-(U55-DO)") (class "Default")
      (node (ref "U55") (pin "1") (pinfunction "DO_1") (pintype "output"))
      (node (ref "U56") (pin "3") (pinfunction "DI_3") (pintype "input"))
    )
    (net (code "72") (name "Net-(U56-DO)") (class "Default")
      (node (ref "U56") (pin "1") (pinfunction "DO_1") (pintype "output"))
      (node (ref "U57") (pin "3") (pinfunction "DI_3") (pintype "input"))
    )
    (net (code "73") (name "Net-(U57-DO)") (class "Default")
      (node (ref "U57") (pin "1") (pinfunction "DO_1") (pintype "output"))
      (node (ref "U58") (pin "3") (pinfunction "DI_3") (pintype "input"))
    )
    (net (code "74") (name "Net-(U58-DO)") (class "Default")
      (node (ref "U58") (pin "1") (pinfunction "DO_1") (pintype "output"))
      (node (ref "U59") (pin "3") (pinfunction "DI_3") (pintype "input"))
    )
    (net (code "75") (name "Net-(U59-DO)") (class "Default")
      (node (ref "U59") (pin "1") (pinfunction "DO_1") (pintype "output"))
      (node (ref "U60") (pin "3") (pinfunction "DI_3") (pintype "input"))
    )
    (net (code "76") (name "Net-(U60-DO)") (class "Default")
      (node (ref "U60") (pin "1") (pinfunction "DO_1") (pintype "output"))
      (node (ref "U61") (pin "3") (pinfunction "DI_3") (pintype "input"))
    )
    (net (code "77") (name "Net-(U61-DO)") (class "Default")
      (node (ref "U61") (pin "1") (pinfunction "DO_1") (pintype "output"))
      (node (ref "U62") (pin "3") (pinfunction "DI_3") (pintype "input"))
    )
    (net (code "78") (name "Net-(U62-DO)") (class "Default")
      (node (ref "U62") (pin "1") (pinfunction "DO_1") (pintype "output"))
      (node (ref "U63") (pin "3") (pinfunction "DI_3") (pintype "input"))
    )
    (net (code "79") (name "Net-(U63-DO)") (class "Default")
      (node (ref "U63") (pin "1") (pinfunction "DO_1") (pintype "output"))
      (node (ref "U64") (pin "3") (pinfunction "DI_3") (pintype "input"))
    )
    (net (code "80") (name "Net-(U64-DO)") (class "Default")
      (node (ref "U64") (pin "1") (pinfunction "DO_1") (pintype "output"))
      (node (ref "U65") (pin "3") (pinfunction "DI_3") (pintype "input"))
    )
    (net (code "81") (name "Net-(U65-DO)") (class "Default")
      (node (ref "U65") (pin "1") (pinfunction "DO_1") (pintype "output"))
      (node (ref "U66") (pin "3") (pinfunction "DI_3") (pintype "input"))
    )
    (net (code "82") (name "Net-(U66-DO)") (class "Default")
      (node (ref "U66") (pin "1") (pinfunction "DO_1") (pintype "output"))
      (node (ref "U67") (pin "3") (pinfunction "DI_3") (pintype "input"))
    )
    (net (code "83") (name "Net-(U67-DO)") (class "Default")
      (node (ref "U67") (pin "1") (pinfunction "DO_1") (pintype "output"))
      (node (ref "U68") (pin "3") (pinfunction "DI_3") (pintype "input"))
    )
    (net (code "84") (name "Net-(U68-DO)") (class "Default")
      (node (ref "U68") (pin "1") (pinfunction "DO_1") (pintype "output"))
      (node (ref "U69") (pin "3") (pinfunction "DI_3") (pintype "input"))
    )
    (net (code "85") (name "Net-(U69-DO)") (class "Default")
      (node (ref "U69") (pin "1") (pinfunction "DO_1") (pintype "output"))
      (node (ref "U70") (pin "3") (pinfunction "DI_3") (pintype "input"))
    )
    (net (code "86") (name "Net-(U70-DO)") (class "Default")
      (node (ref "U70") (pin "1") (pinfunction "DO_1") (pintype "output"))
      (node (ref "U71") (pin "3") (pinfunction "DI_3") (pintype "input"))
    )
    (net (code "87") (name "Net-(U71-DO)") (class "Default")
      (node (ref "U71") (pin "1") (pinfunction "DO_1") (pintype "output"))
      (node (ref "U72") (pin "3") (pinfunction "DI_3") (pintype "input"))
    )
    (net (code "88") (name "Net-(U72-DO)") (class "Default")
      (node (ref "U72") (pin "1") (pinfunction "DO_1") (pintype "output"))
      (node (ref "U73") (pin "3") (pinfunction "DI_3") (pintype "input"))
    )
    (net (code "89") (name "Net-(U73-DO)") (class "Default")
      (node (ref "U73") (pin "1") (pinfunction "DO_1") (pintype "output"))
      (node (ref "U74") (pin "3") (pinfunction "DI_3") (pintype "input"))
    )
    (net (code "90") (name "Net-(U74-DO)") (class "Default")
      (node (ref "U74") (pin "1") (pinfunction "DO_1") (pintype "output"))
      (node (ref "U75") (pin "3") (pinfunction "DI_3") (pintype "input"))
    )
    (net (code "91") (name "Net-(U75-DO)") (class "Default")
      (node (ref "U75") (pin "1") (pinfunction "DO_1") (pintype "output"))
      (node (ref "U76") (pin "3") (pinfunction "DI_3") (pintype "input"))
    )
    (net (code "92") (name "Net-(U76-DO)") (class "Default")
      (node (ref "U76") (pin "1") (pinfunction "DO_1") (pintype "output"))
      (node (ref "U77") (pin "3") (pinfunction "DI_3") (pintype "input"))
    )
    (net (code "93") (name "Net-(U77-DO)") (class "Default")
      (node (ref "U77") (pin "1") (pinfunction "DO_1") (pintype "output"))
      (node (ref "U78") (pin "3") (pinfunction "DI_3") (pintype "input"))
    )
    (net (code "94") (name "Net-(U78-DO)") (class "Default")
      (node (ref "U78") (pin "1") (pinfunction "DO_1") (pintype "output"))
      (node (ref "U79") (pin "3") (pinfunction "DI_3") (pintype "input"))
    )
    (net (code "95") (name "Net-(U79-DO)") (class "Default")
      (node (ref "U79") (pin "1") (pinfunction "DO_1") (pintype "output"))
      (node (ref "U80") (pin "3") (pinfunction "DI_3") (pintype "input"))
    )
    (net (code "96") (name "Net-(U80-DO)") (class "Default")
      (node (ref "U80") (pin "1") (pinfunction "DO_1") (pintype "output"))
      (node (ref "U81") (pin "3") (pinfunction "DI_3") (pintype "input"))
    )
    (net (code "97") (name "Net-(U81-DO)") (class "Default")
      (node (ref "U81") (pin "1") (pinfunction "DO_1") (pintype "output"))
      (node (ref "U82") (pin "3") (pinfunction "DI_3") (pintype "input"))
    )
    (net (code "98") (name "VCC") (class "Default")
      (node (ref "C1") (pin "2") (pinfunction "2_2") (pintype "passive"))
      (node (ref "C2") (pin "2") (pinfunction "2_2") (pintype "passive"))
      (node (ref "C3") (pin "2") (pinfunction "2_2") (pintype "passive"))
      (node (ref "C4") (pin "2") (pinfunction "2_2") (pintype "passive"))
      (node (ref "FB1") (pin "1") (pinfunction "1_1") (pintype "passive"))
      (node (ref "J1") (pin "1") (pinfunction "1_1") (pintype "passive"))
      (node (ref "R1") (pin "2") (pinfunction "1_2") (pintype "passive"))
      (node (ref "SW1") (pin "5") (pinfunction "5_5") (pintype "passive"))
      (node (ref "U1") (pin "18") (pinfunction "AVCC_18") (pintype "power_in"))
      (node (ref "U1") (pin "4") (pinfunction "VCC_4") (pintype "power_in"))
      (node (ref "U1") (pin "6") (pinfunction "VCC_6") (pintype "power_in"))
      (node (ref "U10") (pin "4") (pinfunction "VDD_4") (pintype "power_in"))
      (node (ref "U11") (pin "4") (pinfunction "VDD_4") (pintype "power_in"))
      (node (ref "U12") (pin "4") (pinfunction "VDD_4") (pintype "power_in"))
      (node (ref "U13") (pin "4") (pinfunction "VDD_4") (pintype "power_in"))
      (node (ref "U14") (pin "4") (pinfunction "VDD_4") (pintype "power_in"))
      (node (ref "U15") (pin "4") (pinfunction "VDD_4") (pintype "power_in"))
      (node (ref "U16") (pin "4") (pinfunction "VDD_4") (pintype "power_in"))
      (node (ref "U17") (pin "4") (pinfunction "VDD_4") (pintype "power_in"))
      (node (ref "U18") (pin "4") (pinfunction "VDD_4") (pintype "power_in"))
      (node (ref "U19") (pin "4") (pinfunction "VDD_4") (pintype "power_in"))
      (node (ref "U2") (pin "4") (pinfunction "VDD_4") (pintype "power_in"))
      (node (ref "U20") (pin "4") (pinfunction "VDD_4") (pintype "power_in"))
      (node (ref "U21") (pin "4") (pinfunction "VDD_4") (pintype "power_in"))
      (node (ref "U22") (pin "4") (pinfunction "VDD_4") (pintype "power_in"))
      (node (ref "U23") (pin "4") (pinfunction "VDD_4") (pintype "power_in"))
      (node (ref "U24") (pin "4") (pinfunction "VDD_4") (pintype "power_in"))
      (node (ref "U25") (pin "4") (pinfunction "VDD_4") (pintype "power_in"))
      (node (ref "U26") (pin "4") (pinfunction "VDD_4") (pintype "power_in"))
      (node (ref "U27") (pin "4") (pinfunction "VDD_4") (pintype "power_in"))
      (node (ref "U28") (pin "4") (pinfunction "VDD_4") (pintype "power_in"))
      (node (ref "U29") (pin "4") (pinfunction "VDD_4") (pintype "power_in"))
      (node (ref "U3") (pin "4") (pinfunction "VDD_4") (pintype "power_in"))
      (node (ref "U30") (pin "4") (pinfunction "VDD_4") (pintype "power_in"))
      (node (ref "U31") (pin "4") (pinfunction "VDD_4") (pintype "power_in"))
      (node (ref "U32") (pin "4") (pinfunction "VDD_4") (pintype "power_in"))
      (node (ref "U33") (pin "4") (pinfunction "VDD_4") (pintype "power_in"))
      (node (ref "U34") (pin "4") (pinfunction "VDD_4") (pintype "power_in"))
      (node (ref "U35") (pin "4") (pinfunction "VDD_4") (pintype "power_in"))
      (node (ref "U36") (pin "4") (pinfunction "VDD_4") (pintype "power_in"))
      (node (ref "U37") (pin "4") (pinfunction "VDD_4") (pintype "power_in"))
      (node (ref "U38") (pin "4") (pinfunction "VDD_4") (pintype "power_in"))
      (node (ref "U39") (pin "4") (pinfunction "VDD_4") (pintype "power_in"))
      (node (ref "U4") (pin "4") (pinfunction "VDD_4") (pintype "power_in"))
      (node (ref "U40") (pin "4") (pinfunction "VDD_4") (pintype "power_in"))
      (node (ref "U41") (pin "4") (pinfunction "VDD_4") (pintype "power_in"))
      (node (ref "U42") (pin "4") (pinfunction "VDD_4") (pintype "power_in"))
      (node (ref "U43") (pin "4") (pinfunction "VDD_4") (pintype "power_in"))
      (node (ref "U44") (pin "4") (pinfunction "VDD_4") (pintype "power_in"))
      (node (ref "U45") (pin "4") (pinfunction "VDD_4") (pintype "power_in"))
      (node (ref "U46") (pin "4") (pinfunction "VDD_4") (pintype "power_in"))
      (node (ref "U47") (pin "4") (pinfunction "VDD_4") (pintype "power_in"))
      (node (ref "U48") (pin "4") (pinfunction "VDD_4") (pintype "power_in"))
      (node (ref "U49") (pin "4") (pinfunction "VDD_4") (pintype "power_in"))
      (node (ref "U5") (pin "4") (pinfunction "VDD_4") (pintype "power_in"))
      (node (ref "U50") (pin "4") (pinfunction "VDD_4") (pintype "power_in"))
      (node (ref "U51") (pin "4") (pinfunction "VDD_4") (pintype "power_in"))
      (node (ref "U52") (pin "4") (pinfunction "VDD_4") (pintype "power_in"))
      (node (ref "U53") (pin "4") (pinfunction "VDD_4") (pintype "power_in"))
      (node (ref "U54") (pin "4") (pinfunction "VDD_4") (pintype "power_in"))
      (node (ref "U55") (pin "4") (pinfunction "VDD_4") (pintype "power_in"))
      (node (ref "U56") (pin "4") (pinfunction "VDD_4") (pintype "power_in"))
      (node (ref "U57") (pin "4") (pinfunction "VDD_4") (pintype "power_in"))
      (node (ref "U58") (pin "4") (pinfunction "VDD_4") (pintype "power_in"))
      (node (ref "U59") (pin "4") (pinfunction "VDD_4") (pintype "power_in"))
      (node (ref "U6") (pin "4") (pinfunction "VDD_4") (pintype "power_in"))
      (node (ref "U60") (pin "4") (pinfunction "VDD_4") (pintype "power_in"))
      (node (ref "U61") (pin "4") (pinfunction "VDD_4") (pintype "power_in"))
      (node (ref "U62") (pin "4") (pinfunction "VDD_4") (pintype "power_in"))
      (node (ref "U63") (pin "4") (pinfunction "VDD_4") (pintype "power_in"))
      (node (ref "U64") (pin "4") (pinfunction "VDD_4") (pintype "power_in"))
      (node (ref "U65") (pin "4") (pinfunction "VDD_4") (pintype "power_in"))
      (node (ref "U66") (pin "4") (pinfunction "VDD_4") (pintype "power_in"))
      (node (ref "U67") (pin "4") (pinfunction "VDD_4") (pintype "power_in"))
      (node (ref "U68") (pin "4") (pinfunction "VDD_4") (pintype "power_in"))
      (node (ref "U69") (pin "4") (pinfunction "VDD_4") (pintype "power_in"))
      (node (ref "U7") (pin "4") (pinfunction "VDD_4") (pintype "power_in"))
      (node (ref "U70") (pin "4") (pinfunction "VDD_4") (pintype "power_in"))
      (node (ref "U71") (pin "4") (pinfunction "VDD_4") (pintype "power_in"))
      (node (ref "U72") (pin "4") (pinfunction "VDD_4") (pintype "power_in"))
      (node (ref "U73") (pin "4") (pinfunction "VDD_4") (pintype "power_in"))
      (node (ref "U74") (pin "4") (pinfunction "VDD_4") (pintype "power_in"))
      (node (ref "U75") (pin "4") (pinfunction "VDD_4") (pintype "power_in"))
      (node (ref "U76") (pin "4") (pinfunction "VDD_4") (pintype "power_in"))
      (node (ref "U77") (pin "4") (pinfunction "VDD_4") (pintype "power_in"))
      (node (ref "U78") (pin "4") (pinfunction "VDD_4") (pintype "power_in"))
      (node (ref "U79") (pin "4") (pinfunction "VDD_4") (pintype "power_in"))
      (node (ref "U8") (pin "4") (pinfunction "VDD_4") (pintype "power_in"))
      (node (ref "U80") (pin "4") (pinfunction "VDD_4") (pintype "power_in"))
      (node (ref "U81") (pin "4") (pinfunction "VDD_4") (pintype "power_in"))
      (node (ref "U82") (pin "4") (pinfunction "VDD_4") (pintype "power_in"))
      (node (ref "U9") (pin "4") (pinfunction "VDD_4") (pintype "power_in"))
    )
    (net (code "99") (name "unconnected-(J2-D+-Pad3)") (class "Default")
      (node (ref "J2") (pin "3") (pinfunction "D+_3") (pintype "passive"))
    )
    (net (code "100") (name "unconnected-(J2-D--Pad2)") (class "Default")
      (node (ref "J2") (pin "2") (pinfunction "D-_2") (pintype "passive"))
    )
    (net (code "101") (name "unconnected-(J2-ID-Pad4)") (class "Default")
      (node (ref "J2") (pin "4") (pinfunction "ID_4") (pintype "passive"))
    )
    (net (code "102") (name "unconnected-(J2-SHLD1-Pad6)") (class "Default")
      (node (ref "J2") (pin "6") (pinfunction "SHLD1_6") (pintype "passive"))
    )
    (net (code "103") (name "unconnected-(J2-SHLD2-Pad7)") (class "Default")
      (node (ref "J2") (pin "7") (pinfunction "SHLD2_7") (pintype "passive"))
    )
    (net (code "104") (name "unconnected-(J2-SHLD3-Pad8)") (class "Default")
      (node (ref "J2") (pin "8") (pinfunction "SHLD3_8") (pintype "passive"))
    )
    (net (code "105") (name "unconnected-(J2-SHLD4-Pad9)") (class "Default")
      (node (ref "J2") (pin "9") (pinfunction "SHLD4_9") (pintype "passive"))
    )
    (net (code "106") (name "unconnected-(J2-SHLD5-Pad10)") (class "Default")
      (node (ref "J2") (pin "10") (pinfunction "SHLD5_10") (pintype "passive"))
    )
    (net (code "107") (name "unconnected-(J2-SHLD6-Pad11)") (class "Default")
      (node (ref "J2") (pin "11") (pinfunction "SHLD6_11") (pintype "passive"))
    )
    (net (code "108") (name "unconnected-(U1-(PCINT0{slash}CLKO{slash}ICP1)PB0-Pad12)") (class "Default")
      (node (ref "U1") (pin "12") (pinfunction "(PCINT0/CLKO/ICP1)PB0_12") (pintype "bidirectional"))
    )
    (net (code "109") (name "unconnected-(U1-(PCINT1{slash}OC1A)PB1-Pad13)") (class "Default")
      (node (ref "U1") (pin "13") (pinfunction "(PCINT1/OC1A)PB1_13") (pintype "bidirectional"))
    )
    (net (code "110") (name "unconnected-(U1-(PCINT2{slash}~{SS}{slash}OC1B)PB2-Pad14)") (class "Default")
      (node (ref "U1") (pin "14") (pinfunction "(PCINT2/~{SS}/OC1B)PB2_14") (pintype "bidirectional"))
    )
    (net (code "111") (name "unconnected-(U1-(PCINT19{slash}OC2B{slash}INT1)PD3-Pad1)") (class "Default")
      (node (ref "U1") (pin "1") (pinfunction "(PCINT19/OC2B/INT1)PD3_1") (pintype "bidirectional"))
    )
    (net (code "112") (name "unconnected-(U1-(PCINT20{slash}XCK{slash}T0)PD4-Pad2)") (class "Default")
      (node (ref "U1") (pin "2") (pinfunction "(PCINT20/XCK/T0)PD4_2") (pintype "bidirectional"))
    )
    (net (code "113") (name "unconnected-(U1-(PCINT21{slash}OC0B{slash}T1)PD5-Pad9)") (class "Default")
      (node (ref "U1") (pin "9") (pinfunction "(PCINT21/OC0B/T1)PD5_9") (pintype "bidirectional"))
    )
    (net (code "114") (name "unconnected-(U1-(PCINT22{slash}OC0A{slash}AIN0)PD6-Pad10)") (class "Default")
      (node (ref "U1") (pin "10") (pinfunction "(PCINT22/OC0A/AIN0)PD6_10") (pintype "bidirectional"))
    )
    (net (code "115") (name "unconnected-(U1-(PCINT23{slash}AIN1)PD7-Pad11)") (class "Default")
      (node (ref "U1") (pin "11") (pinfunction "(PCINT23/AIN1)PD7_11") (pintype "bidirectional"))
    )
    (net (code "116") (name "unconnected-(U1-ADC6-Pad19)") (class "Default")
      (node (ref "U1") (pin "19") (pinfunction "ADC6_19") (pintype "power_in"))
    )
    (net (code "117") (name "unconnected-(U1-ADC7-Pad22)") (class "Default")
      (node (ref "U1") (pin "22") (pinfunction "ADC7_22") (pintype "passive"))
    )
    (net (code "118") (name "unconnected-(U1-AREF-Pad20)") (class "Default")
      (node (ref "U1") (pin "20") (pinfunction "AREF_20") (pintype "passive"))
    )
    (net (code "119") (name "unconnected-(U1-PC5(ADC5{slash}SCL{slash}PCINT13)-Pad28)") (class "Default")
      (node (ref "U1") (pin "28") (pinfunction "PC5(ADC5/SCL/PCINT13)_28") (pintype "bidirectional"))
    )
    (net (code "120") (name "unconnected-(U4-GND-Pad2)") (class "Default")
      (node (ref "U4") (pin "2") (pinfunction "GND_2") (pintype "power_in"))
    )
    (net (code "121") (name "unconnected-(U15-GND-Pad2)") (class "Default")
      (node (ref "U15") (pin "2") (pinfunction "GND_2") (pintype "power_in"))
    )
    (net (code "122") (name "unconnected-(U82-DO-Pad1)") (class "Default")
      (node (ref "U82") (pin "1") (pinfunction "DO_1") (pintype "output"))
    )
  )
)
